# Sensor_Board_0d0ac80375c143579a8476edc31.net
KiCad netlist of a schematic drawn in EAGLE
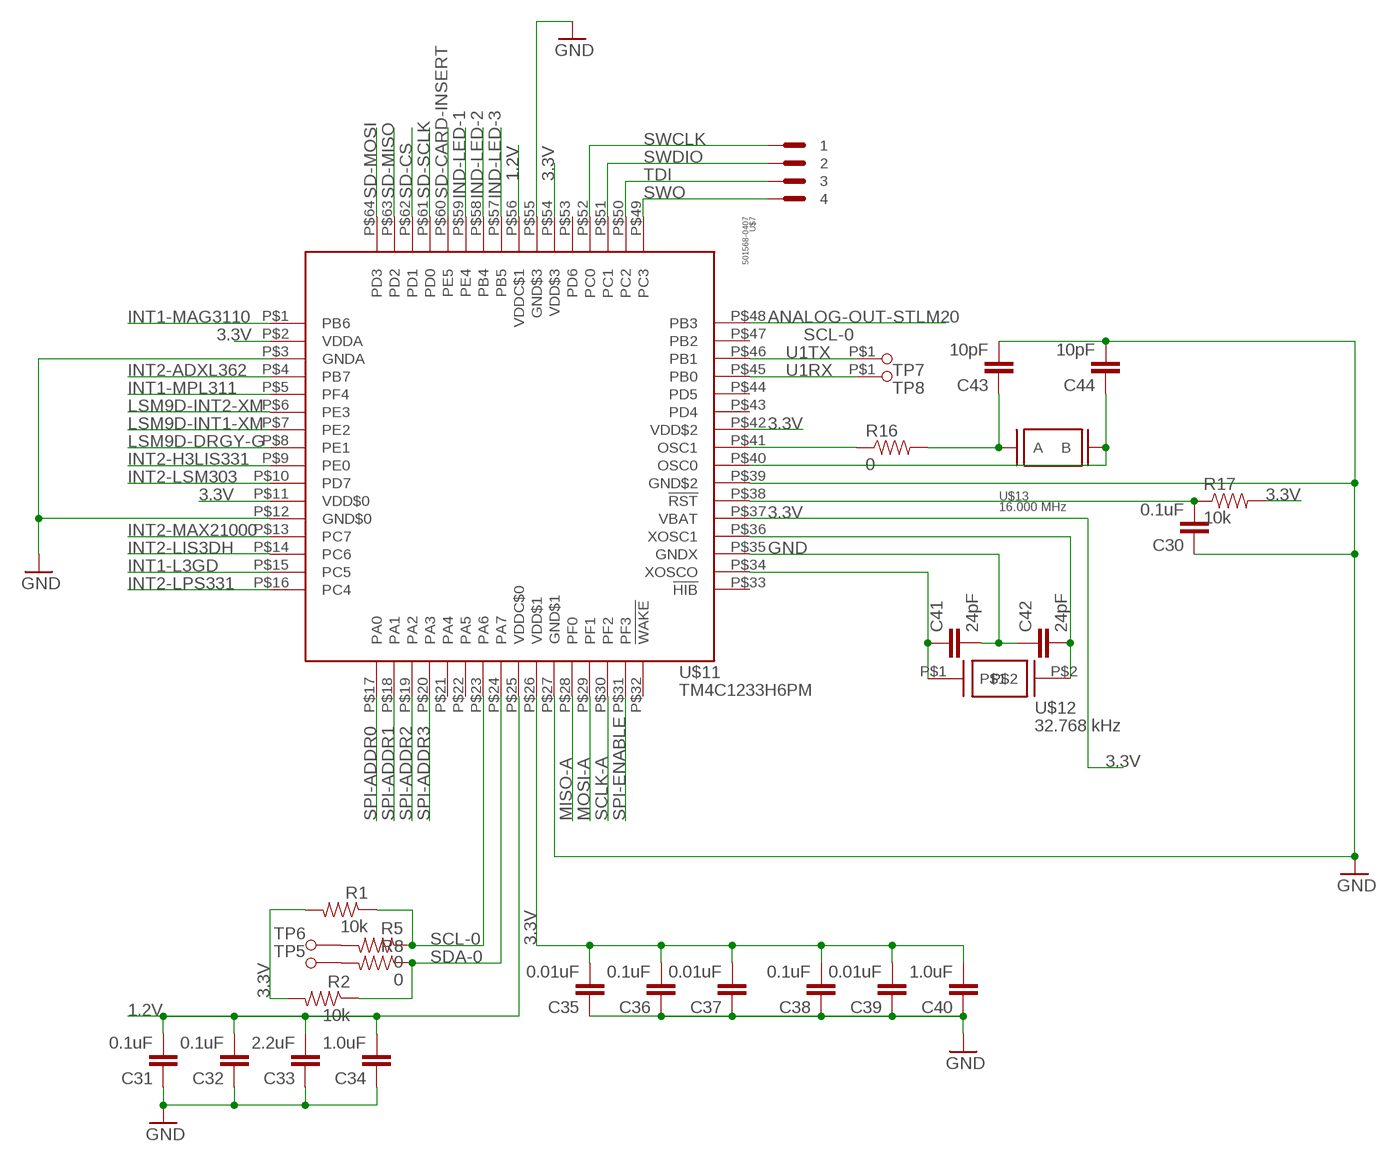
[diagram p0: schematic, sheet 1]
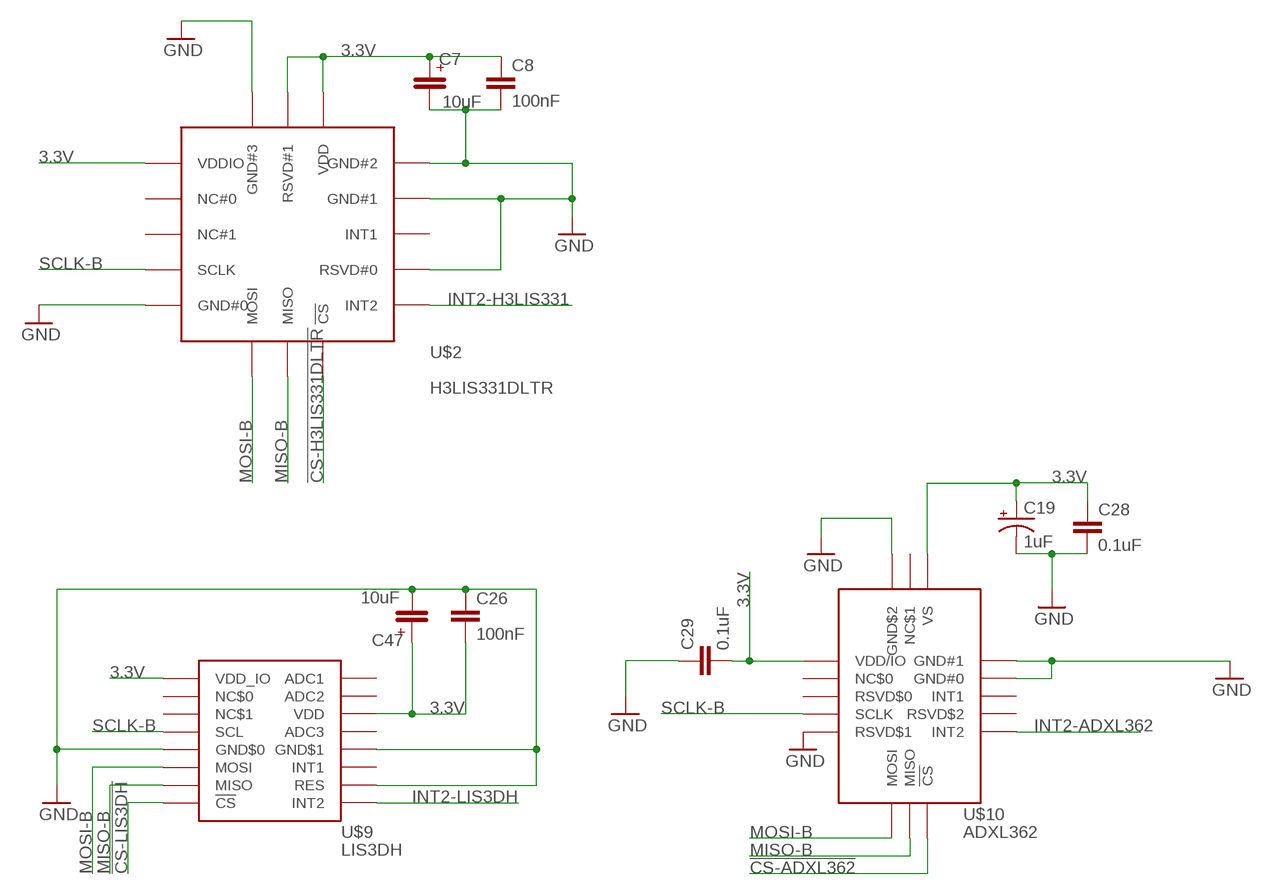
[diagram p1: schematic, sheet 2]
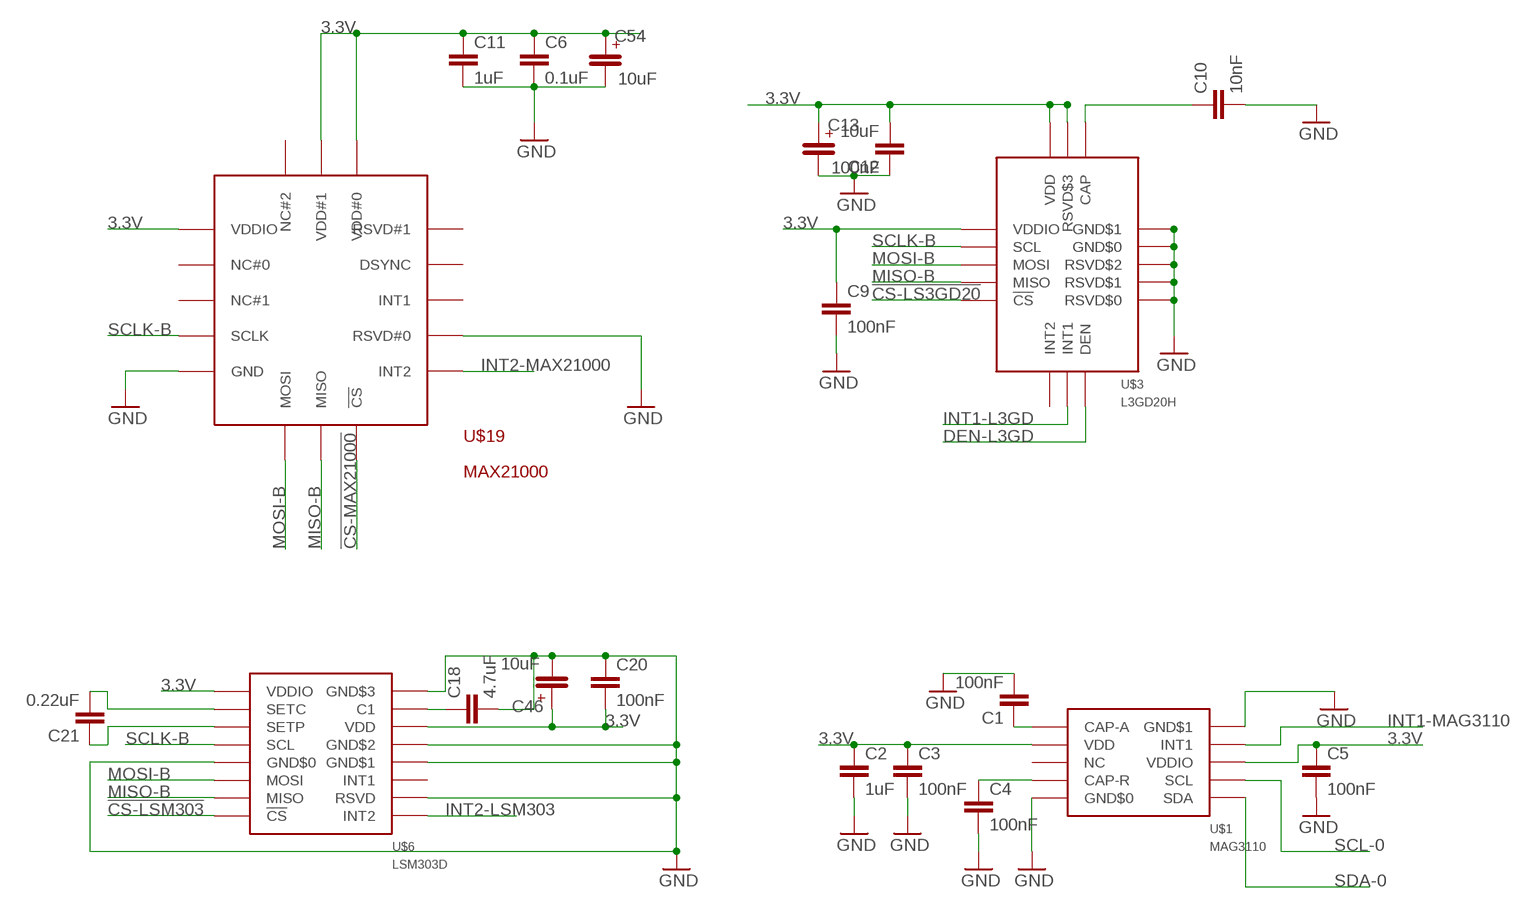
[diagram p2: schematic, sheet 3]
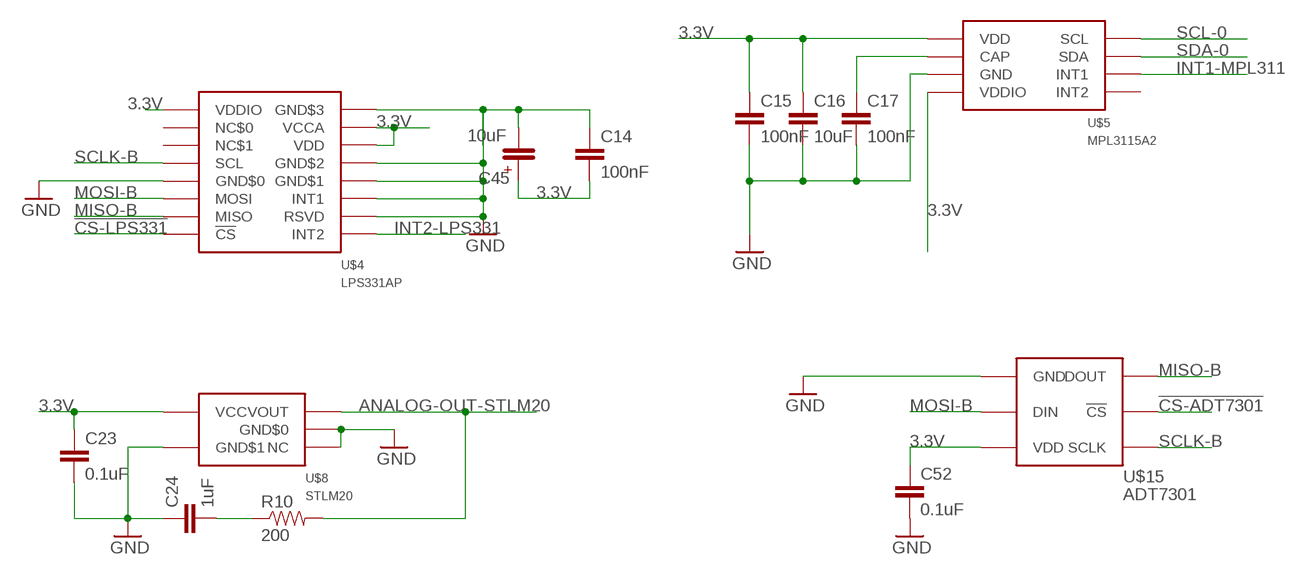
[diagram p3: schematic, sheet 4]
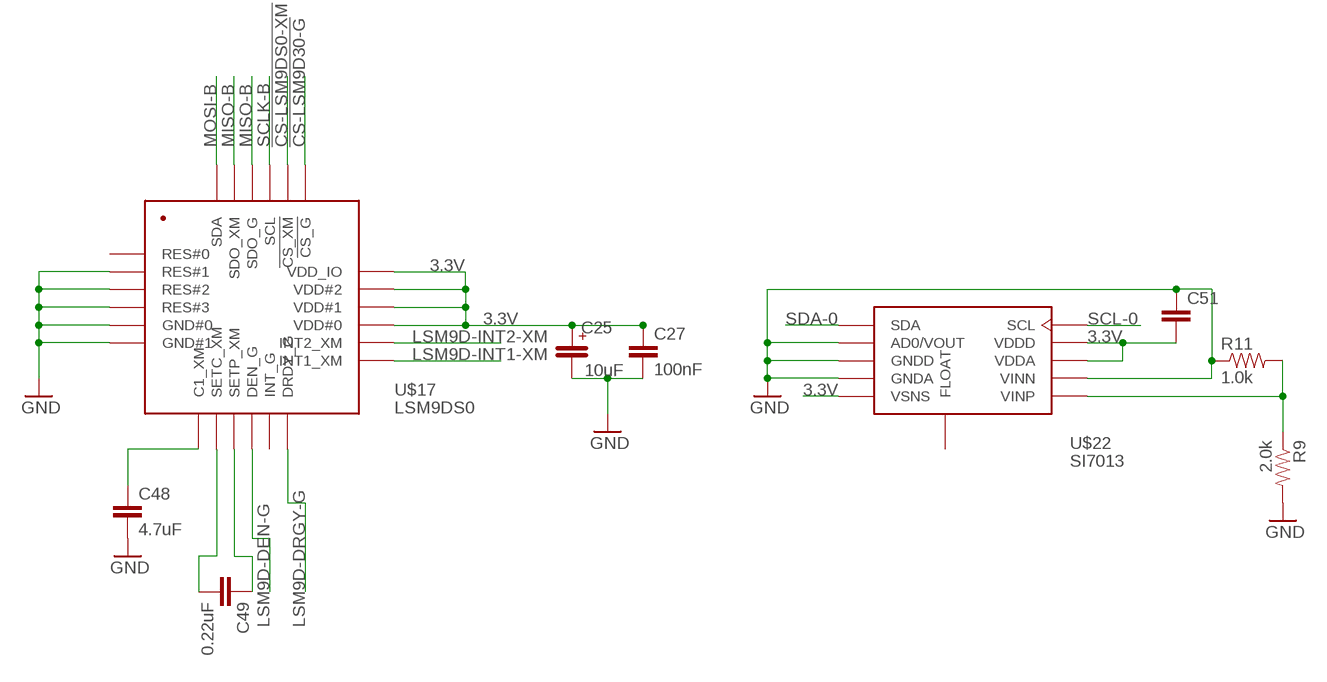
[diagram p4: schematic, sheet 5]
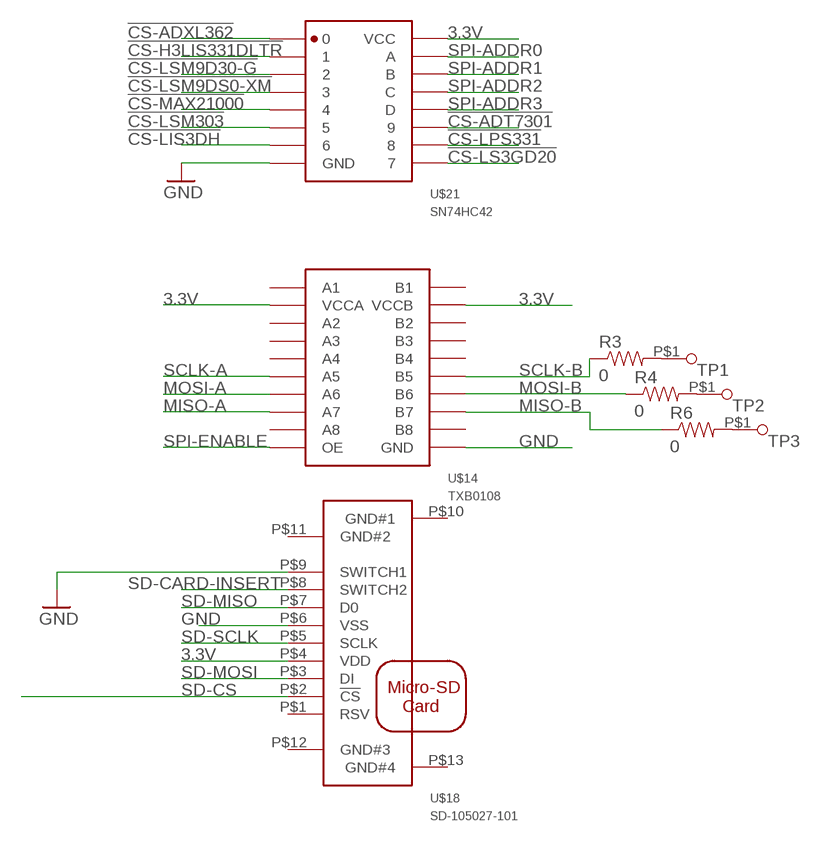
[diagram p5: schematic, sheet 6]
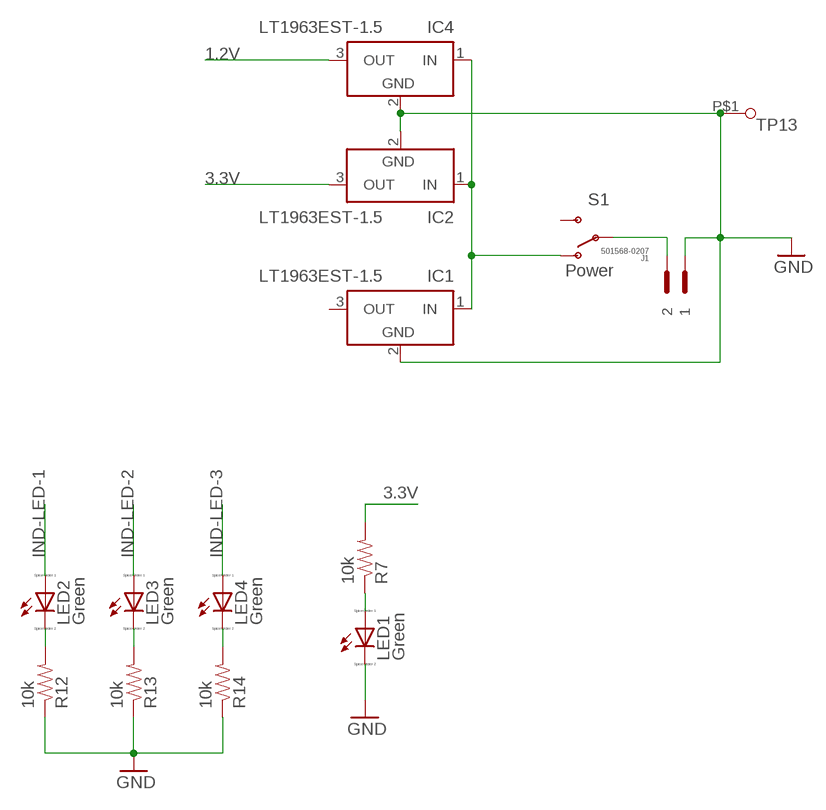
[diagram p6: schematic, sheet 7]

(export (version "E")
  (design (tool "Eeschema 10.0.6"))
  (components
    (comp (ref "C7")
      (value "10uF")
      (footprint "eagle-import:4.3X7.3SMD")
      (libsource (lib "eagle-import") (part "EEFCD0J100ER"))
    )
    (comp (ref "C8")
      (value "100nF")
      (footprint "eagle-import:C0402")
      (libsource (lib "eagle-import") (part "CAPACITOR0402"))
    )
    (comp (ref "C19")
      (value "1uF")
      (footprint "eagle-import:EIA6032")
      (libsource (lib "eagle-import") (part "CAP_POL6032"))
    )
    (comp (ref "C26")
      (value "100nF")
      (footprint "eagle-import:C0402")
      (libsource (lib "eagle-import") (part "CAPACITOR0402"))
    )
    (comp (ref "C28")
      (value "0.1uF")
      (footprint "eagle-import:C0402")
      (libsource (lib "eagle-import") (part "CAPACITOR0402"))
    )
    (comp (ref "C29")
      (value "0.1uF")
      (footprint "eagle-import:C0402")
      (libsource (lib "eagle-import") (part "CAPACITOR0402"))
    )
    (comp (ref "C47")
      (value "10uF")
      (footprint "eagle-import:4.3X7.3SMD")
      (libsource (lib "eagle-import") (part "EEFCD0J100ER"))
    )
    (comp (ref "U$2")
      (value "H3LIS331DLTR")
      (footprint "eagle-import:LGA-16(3X3)")
      (libsource (lib "eagle-import") (part "H3LIS331DLTR"))
    )
    (comp (ref "U$9")
      (value "LIS3DH")
      (footprint "eagle-import:LGA-16(3X3)")
      (libsource (lib "eagle-import") (part "LIS3DH"))
    )
    (comp (ref "U$10")
      (value "ADXL362")
      (footprint "eagle-import:LGA-16(3X3.25)")
      (libsource (lib "eagle-import") (part "ADXL362"))
    )
    (comp (ref "C25")
      (value "10uF")
      (footprint "eagle-import:4.3X7.3SMD")
      (libsource (lib "eagle-import") (part "EEFCD0J100ER"))
    )
    (comp (ref "C27")
      (value "100nF")
      (footprint "eagle-import:C0402")
      (libsource (lib "eagle-import") (part "CAPACITOR0402"))
    )
    (comp (ref "C48")
      (value "4.7uF")
      (footprint "eagle-import:C0402")
      (libsource (lib "eagle-import") (part "CAPACITOR0402"))
    )
    (comp (ref "C49")
      (value "0.22uF")
      (footprint "eagle-import:C0402")
      (libsource (lib "eagle-import") (part "CAPACITOR0402"))
    )
    (comp (ref "C51")
      (value "CAPACITOR0402")
      (footprint "eagle-import:C0402")
      (libsource (lib "eagle-import") (part "CAPACITOR0402"))
    )
    (comp (ref "R9")
      (value "2.0k")
      (footprint "eagle-import:R0402")
      (libsource (lib "eagle-import") (part "RESISTOR"))
    )
    (comp (ref "R11")
      (value "1.0k")
      (footprint "eagle-import:R0402")
      (libsource (lib "eagle-import") (part "RESISTOR"))
    )
    (comp (ref "U$17")
      (value "LSM9DS0")
      (footprint "eagle-import:LGA-24(4X4)")
      (libsource (lib "eagle-import") (part "LSM9DS0"))
    )
    (comp (ref "U$22")
      (value "SI7013")
      (footprint "eagle-import:DFN-10(3X3)")
      (libsource (lib "eagle-import") (part "SI7013"))
    )
    (comp (ref "C1")
      (value "100nF")
      (footprint "eagle-import:C0402")
      (libsource (lib "eagle-import") (part "CAPACITOR0402"))
    )
    (comp (ref "C2")
      (value "1uF")
      (footprint "eagle-import:C0402")
      (libsource (lib "eagle-import") (part "CAPACITOR0402"))
    )
    (comp (ref "C3")
      (value "100nF")
      (footprint "eagle-import:C0402")
      (libsource (lib "eagle-import") (part "CAPACITOR0402"))
    )
    (comp (ref "C4")
      (value "100nF")
      (footprint "eagle-import:C0402")
      (libsource (lib "eagle-import") (part "CAPACITOR0402"))
    )
    (comp (ref "C5")
      (value "100nF")
      (footprint "eagle-import:C0402")
      (libsource (lib "eagle-import") (part "CAPACITOR0402"))
    )
    (comp (ref "C6")
      (value "0.1uF")
      (footprint "eagle-import:C0402")
      (libsource (lib "eagle-import") (part "CAPACITOR0402"))
    )
    (comp (ref "C9")
      (value "100nF")
      (footprint "eagle-import:C0402")
      (libsource (lib "eagle-import") (part "CAPACITOR0402"))
    )
    (comp (ref "C10")
      (value "10nF")
      (footprint "eagle-import:C0402")
      (libsource (lib "eagle-import") (part "CAPACITOR0402"))
    )
    (comp (ref "C11")
      (value "1uF")
      (footprint "eagle-import:C0402")
      (libsource (lib "eagle-import") (part "CAPACITOR0402"))
    )
    (comp (ref "C12")
      (value "10uF")
      (footprint "eagle-import:C0402")
      (libsource (lib "eagle-import") (part "CAPACITOR0402"))
    )
    (comp (ref "C13")
      (value "100nF")
      (footprint "eagle-import:4.3X7.3SMD")
      (libsource (lib "eagle-import") (part "EEFCD0J100ER"))
    )
    (comp (ref "C18")
      (value "4.7uF")
      (footprint "eagle-import:C0402")
      (libsource (lib "eagle-import") (part "CAPACITOR0402"))
    )
    (comp (ref "C20")
      (value "100nF")
      (footprint "eagle-import:C0402")
      (libsource (lib "eagle-import") (part "CAPACITOR0402"))
    )
    (comp (ref "C21")
      (value "0.22uF")
      (footprint "eagle-import:C0402")
      (libsource (lib "eagle-import") (part "CAPACITOR0402"))
    )
    (comp (ref "C46")
      (value "10uF")
      (footprint "eagle-import:4.3X7.3SMD")
      (libsource (lib "eagle-import") (part "EEFCD0J100ER"))
    )
    (comp (ref "C54")
      (value "10uF")
      (footprint "eagle-import:4.3X7.3SMD")
      (libsource (lib "eagle-import") (part "EEFCD0J100ER"))
    )
    (comp (ref "U$1")
      (value "MAG3110")
      (footprint "eagle-import:DFN-10(2X2)")
      (libsource (lib "eagle-import") (part "MAG3110"))
    )
    (comp (ref "U$3")
      (value "L3GD20H")
      (footprint "eagle-import:LGA-16(3X3)")
      (libsource (lib "eagle-import") (part "L3GD20H"))
    )
    (comp (ref "U$6")
      (value "LSM303D")
      (footprint "eagle-import:LGA-16(3X3)")
      (libsource (lib "eagle-import") (part "LSM303D"))
    )
    (comp (ref "U$19")
      (value "MAX21000")
      (footprint "eagle-import:LGA-16(3X3)")
      (libsource (lib "eagle-import") (part "MAX21000"))
    )
    (comp (ref "C14")
      (value "100nF")
      (footprint "eagle-import:C0402")
      (libsource (lib "eagle-import") (part "CAPACITOR0402"))
    )
    (comp (ref "C15")
      (value "100nF")
      (footprint "eagle-import:C0402")
      (libsource (lib "eagle-import") (part "CAPACITOR0402"))
    )
    (comp (ref "C16")
      (value "10uF")
      (footprint "eagle-import:C0402")
      (libsource (lib "eagle-import") (part "CAPACITOR0402"))
    )
    (comp (ref "C17")
      (value "100nF")
      (footprint "eagle-import:C0402")
      (libsource (lib "eagle-import") (part "CAPACITOR0402"))
    )
    (comp (ref "C23")
      (value "0.1uF")
      (footprint "eagle-import:C0402")
      (libsource (lib "eagle-import") (part "CAPACITOR0402"))
    )
    (comp (ref "C24")
      (value "1uF")
      (footprint "eagle-import:C0402")
      (libsource (lib "eagle-import") (part "CAPACITOR0402"))
    )
    (comp (ref "C45")
      (value "10uF")
      (footprint "eagle-import:4.3X7.3SMD")
      (libsource (lib "eagle-import") (part "EEFCD0J100ER"))
    )
    (comp (ref "C52")
      (value "0.1uF")
      (footprint "eagle-import:C0402")
      (libsource (lib "eagle-import") (part "CAPACITOR0402"))
    )
    (comp (ref "R10")
      (value "200")
      (footprint "eagle-import:R0402")
      (libsource (lib "eagle-import") (part "RESISTOR"))
    )
    (comp (ref "U$4")
      (value "LPS331AP")
      (footprint "eagle-import:LGA-16(3X3)")
      (libsource (lib "eagle-import") (part "LPS331AP"))
    )
    (comp (ref "U$5")
      (value "MPL3115A2")
      (footprint "eagle-import:LGA-8(5X3)")
      (libsource (lib "eagle-import") (part "MPL3115A2"))
    )
    (comp (ref "U$8")
      (value "STLM20")
      (footprint "eagle-import:SOT323-5L")
      (libsource (lib "eagle-import") (part "STLM20"))
    )
    (comp (ref "U$15")
      (value "ADT7301")
      (footprint "eagle-import:SOT23-6")
      (libsource (lib "eagle-import") (part "ADT7301"))
    )
    (comp (ref "C30")
      (value "0.1uF")
      (footprint "eagle-import:C0402")
      (libsource (lib "eagle-import") (part "CAPACITOR0402"))
    )
    (comp (ref "C31")
      (value "0.1uF")
      (footprint "eagle-import:C0402")
      (libsource (lib "eagle-import") (part "CAPACITOR0402"))
    )
    (comp (ref "C32")
      (value "0.1uF")
      (footprint "eagle-import:C0402")
      (libsource (lib "eagle-import") (part "CAPACITOR0402"))
    )
    (comp (ref "C33")
      (value "2.2uF")
      (footprint "eagle-import:C0402")
      (libsource (lib "eagle-import") (part "CAPACITOR0402"))
    )
    (comp (ref "C34")
      (value "1.0uF")
      (footprint "eagle-import:C0402")
      (libsource (lib "eagle-import") (part "CAPACITOR0402"))
    )
    (comp (ref "C35")
      (value "0.01uF")
      (footprint "eagle-import:C0402")
      (libsource (lib "eagle-import") (part "CAPACITOR0402"))
    )
    (comp (ref "C36")
      (value "0.1uF")
      (footprint "eagle-import:C0402")
      (libsource (lib "eagle-import") (part "CAPACITOR0402"))
    )
    (comp (ref "C37")
      (value "0.01uF")
      (footprint "eagle-import:C0402")
      (libsource (lib "eagle-import") (part "CAPACITOR0402"))
    )
    (comp (ref "C38")
      (value "0.1uF")
      (footprint "eagle-import:C0402")
      (libsource (lib "eagle-import") (part "CAPACITOR0402"))
    )
    (comp (ref "C39")
      (value "0.01uF")
      (footprint "eagle-import:C0402")
      (libsource (lib "eagle-import") (part "CAPACITOR0402"))
    )
    (comp (ref "C40")
      (value "1.0uF")
      (footprint "eagle-import:C0402")
      (libsource (lib "eagle-import") (part "CAPACITOR0402"))
    )
    (comp (ref "C41")
      (value "24pF")
      (footprint "eagle-import:C0402")
      (libsource (lib "eagle-import") (part "CAPACITOR0402"))
    )
    (comp (ref "C42")
      (value "24pF")
      (footprint "eagle-import:C0402")
      (libsource (lib "eagle-import") (part "CAPACITOR0402"))
    )
    (comp (ref "C43")
      (value "10pF")
      (footprint "eagle-import:C0402")
      (libsource (lib "eagle-import") (part "CAPACITOR0402"))
    )
    (comp (ref "C44")
      (value "10pF")
      (footprint "eagle-import:C0402")
      (libsource (lib "eagle-import") (part "CAPACITOR0402"))
    )
    (comp (ref "R1")
      (value "10k")
      (footprint "eagle-import:R0402")
      (libsource (lib "eagle-import") (part "RESISTOR"))
    )
    (comp (ref "R2")
      (value "10k")
      (footprint "eagle-import:R0402")
      (libsource (lib "eagle-import") (part "RESISTOR"))
    )
    (comp (ref "R5")
      (value "0")
      (footprint "eagle-import:R0402")
      (libsource (lib "eagle-import") (part "RESISTOR"))
    )
    (comp (ref "R8")
      (value "0")
      (footprint "eagle-import:R0402")
      (libsource (lib "eagle-import") (part "RESISTOR"))
    )
    (comp (ref "R16")
      (value "0")
      (footprint "eagle-import:R0402")
      (libsource (lib "eagle-import") (part "RESISTOR"))
    )
    (comp (ref "R17")
      (value "10k")
      (footprint "eagle-import:R0402")
      (libsource (lib "eagle-import") (part "RESISTOR"))
    )
    (comp (ref "TP5")
      (value "TESTPAD(ROUND)")
      (footprint "eagle-import:TESTPAD(ROUND)")
      (libsource (lib "eagle-import") (part "TESTPAD(ROUND)"))
    )
    (comp (ref "TP6")
      (value "TESTPAD(ROUND)")
      (footprint "eagle-import:TESTPAD(ROUND)")
      (libsource (lib "eagle-import") (part "TESTPAD(ROUND)"))
    )
    (comp (ref "TP7")
      (value "TESTPAD(ROUND)")
      (footprint "eagle-import:TESTPAD(ROUND)")
      (libsource (lib "eagle-import") (part "Kas-Passives_TESTPAD(ROUND)"))
    )
    (comp (ref "TP8")
      (value "TESTPAD(ROUND)")
      (footprint "eagle-import:TESTPAD(ROUND)")
      (libsource (lib "eagle-import") (part "Kas-Passives_TESTPAD(ROUND)"))
    )
    (comp (ref "U$7")
      (value "501568-0407")
      (footprint "eagle-import:501568-0407")
      (libsource (lib "eagle-import") (part "501568-0407"))
    )
    (comp (ref "U$11")
      (value "TM4C1233H6PM")
      (footprint "eagle-import:S-PQFP-G64")
      (libsource (lib "eagle-import") (part "TM4C1233H6PM"))
    )
    (comp (ref "U$12")
      (value "32.768 kHz")
      (footprint "eagle-import:2-SMD(3.2X1.5)")
      (libsource (lib "eagle-import") (part "ABS07L"))
    )
    (comp (ref "U$13")
      (value "16.000 MHz")
      (footprint "eagle-import:4-SMD(3.2X2.5)")
      (libsource (lib "eagle-import") (part "NX3225GA"))
    )
    (comp (ref "R3")
      (value "0")
      (footprint "eagle-import:R0402")
      (libsource (lib "eagle-import") (part "RESISTOR"))
    )
    (comp (ref "R4")
      (value "0")
      (footprint "eagle-import:R0402")
      (libsource (lib "eagle-import") (part "RESISTOR"))
    )
    (comp (ref "R6")
      (value "0")
      (footprint "eagle-import:R0402")
      (libsource (lib "eagle-import") (part "RESISTOR"))
    )
    (comp (ref "TP1")
      (value "TESTPAD(ROUND)")
      (footprint "eagle-import:TESTPAD(ROUND)")
      (libsource (lib "eagle-import") (part "Kas-Passives_TESTPAD(ROUND)"))
    )
    (comp (ref "TP2")
      (value "TESTPAD(ROUND)")
      (footprint "eagle-import:TESTPAD(ROUND)")
      (libsource (lib "eagle-import") (part "Kas-Passives_TESTPAD(ROUND)"))
    )
    (comp (ref "TP3")
      (value "TESTPAD(ROUND)")
      (footprint "eagle-import:TESTPAD(ROUND)")
      (libsource (lib "eagle-import") (part "Kas-Passives_TESTPAD(ROUND)"))
    )
    (comp (ref "U$14")
      (value "TXB0108")
      (footprint "eagle-import:TSSOP-(PW)-20")
      (libsource (lib "eagle-import") (part "TXB0108"))
    )
    (comp (ref "U$18")
      (value "SD-105027-101")
      (footprint "eagle-import:SD-105027-1001")
      (libsource (lib "eagle-import") (part "SD-105027-101"))
    )
    (comp (ref "U$21")
      (value "SN74HC42")
      (footprint "eagle-import:SOIC-16")
      (libsource (lib "eagle-import") (part "SN74HC42"))
    )
    (comp (ref "IC1")
      (value "LT1963EST-1.5")
      (footprint "eagle-import:SOT223")
      (libsource (lib "eagle-import") (part "LT1963EST-1.5"))
    )
    (comp (ref "IC2")
      (value "LT1963EST-1.5")
      (footprint "eagle-import:SOT223")
      (libsource (lib "eagle-import") (part "LT1963EST-1.5"))
    )
    (comp (ref "IC4")
      (value "LT1963EST-1.5")
      (footprint "eagle-import:SOT223")
      (libsource (lib "eagle-import") (part "LT1963EST-1.5"))
    )
    (comp (ref "J1")
      (value "501568-0207")
      (footprint "eagle-import:501568-0207")
      (libsource (lib "eagle-import") (part "501568-0207"))
    )
    (comp (ref "LED1")
      (value "Green")
      (footprint "eagle-import:LED_SML0603")
      (libsource (lib "eagle-import") (part "LED_ESML0603"))
    )
    (comp (ref "LED2")
      (value "Green")
      (footprint "eagle-import:LED_SML0603")
      (libsource (lib "eagle-import") (part "LED_ESML0603"))
    )
    (comp (ref "LED3")
      (value "Green")
      (footprint "eagle-import:LED_SML0603")
      (libsource (lib "eagle-import") (part "LED_ESML0603"))
    )
    (comp (ref "LED4")
      (value "Green")
      (footprint "eagle-import:LED_SML0603")
      (libsource (lib "eagle-import") (part "LED_ESML0603"))
    )
    (comp (ref "R7")
      (value "10k")
      (footprint "eagle-import:R0402")
      (libsource (lib "eagle-import") (part "RESISTOR"))
    )
    (comp (ref "R12")
      (value "10k")
      (footprint "eagle-import:R0402")
      (libsource (lib "eagle-import") (part "RESISTOR"))
    )
    (comp (ref "R13")
      (value "10k")
      (footprint "eagle-import:R0402")
      (libsource (lib "eagle-import") (part "RESISTOR"))
    )
    (comp (ref "R14")
      (value "10k")
      (footprint "eagle-import:R0402")
      (libsource (lib "eagle-import") (part "RESISTOR"))
    )
    (comp (ref "S1")
      (value "Power")
      (footprint "eagle-import:SWITCH-SPST-SMD-A")
      (libsource (lib "eagle-import") (part "SWITCH-SPDT-SMD-A"))
    )
    (comp (ref "TP13")
      (value "TESTPAD(ROUND)")
      (footprint "eagle-import:TESTPAD(ROUND)")
      (libsource (lib "eagle-import") (part "Kas-Passives_TESTPAD(ROUND)"))
    )
  )
  (nets
    (net (code "1") (name "1.2V") (class "Default")
      (node (ref "C31") (pin "2") (pinfunction "2_2") (pintype "passive"))
      (node (ref "C32") (pin "2") (pinfunction "2_2") (pintype "passive"))
      (node (ref "C33") (pin "2") (pinfunction "2_2") (pintype "passive"))
      (node (ref "C34") (pin "2") (pinfunction "2_2") (pintype "passive"))
      (node (ref "IC4") (pin "3") (pinfunction "OUT_3") (pintype "output"))
      (node (ref "U$11") (pin "P$25") (pinfunction "VDDC$0_P$25") (pintype "bidirectional"))
      (node (ref "U$11") (pin "P$56") (pinfunction "VDDC$1_P$56") (pintype "bidirectional"))
    )
    (net (code "2") (name "3.3V") (class "Default")
      (node (ref "C11") (pin "1") (pinfunction "1_1") (pintype "passive"))
      (node (ref "C12") (pin "2") (pinfunction "2_2") (pintype "passive"))
      (node (ref "C13") (pin "P$1") (pintype "bidirectional"))
      (node (ref "C14") (pin "2") (pinfunction "2_2") (pintype "passive"))
      (node (ref "C15") (pin "1") (pinfunction "1_1") (pintype "passive"))
      (node (ref "C16") (pin "1") (pinfunction "1_1") (pintype "passive"))
      (node (ref "C19") (pin "P$1") (pinfunction "+_P$1") (pintype "passive"))
      (node (ref "C2") (pin "1") (pinfunction "1_1") (pintype "passive"))
      (node (ref "C20") (pin "2") (pinfunction "2_2") (pintype "passive"))
      (node (ref "C23") (pin "1") (pinfunction "1_1") (pintype "passive"))
      (node (ref "C25") (pin "P$1") (pintype "bidirectional"))
      (node (ref "C26") (pin "2") (pinfunction "2_2") (pintype "passive"))
      (node (ref "C27") (pin "1") (pinfunction "1_1") (pintype "passive"))
      (node (ref "C28") (pin "1") (pinfunction "1_1") (pintype "passive"))
      (node (ref "C29") (pin "2") (pinfunction "2_2") (pintype "passive"))
      (node (ref "C3") (pin "1") (pinfunction "1_1") (pintype "passive"))
      (node (ref "C35") (pin "2") (pinfunction "2_2") (pintype "passive"))
      (node (ref "C36") (pin "2") (pinfunction "2_2") (pintype "passive"))
      (node (ref "C37") (pin "2") (pinfunction "2_2") (pintype "passive"))
      (node (ref "C38") (pin "2") (pinfunction "2_2") (pintype "passive"))
      (node (ref "C39") (pin "2") (pinfunction "2_2") (pintype "passive"))
      (node (ref "C40") (pin "2") (pinfunction "2_2") (pintype "passive"))
      (node (ref "C45") (pin "P$1") (pintype "bidirectional"))
      (node (ref "C46") (pin "P$1") (pintype "bidirectional"))
      (node (ref "C47") (pin "P$1") (pintype "bidirectional"))
      (node (ref "C5") (pin "1") (pinfunction "1_1") (pintype "passive"))
      (node (ref "C51") (pin "2") (pinfunction "2_2") (pintype "passive"))
      (node (ref "C52") (pin "1") (pinfunction "1_1") (pintype "passive"))
      (node (ref "C54") (pin "P$1") (pintype "bidirectional"))
      (node (ref "C6") (pin "1") (pinfunction "1_1") (pintype "passive"))
      (node (ref "C7") (pin "P$1") (pintype "bidirectional"))
      (node (ref "C8") (pin "1") (pinfunction "1_1") (pintype "passive"))
      (node (ref "C9") (pin "1") (pinfunction "1_1") (pintype "passive"))
      (node (ref "IC2") (pin "3") (pinfunction "OUT_3") (pintype "output"))
      (node (ref "R1") (pin "2") (pinfunction "2_2") (pintype "passive"))
      (node (ref "R17") (pin "2") (pinfunction "2_2") (pintype "passive"))
      (node (ref "R2") (pin "2") (pinfunction "2_2") (pintype "passive"))
      (node (ref "R7") (pin "2") (pinfunction "2_2") (pintype "passive"))
      (node (ref "U$1") (pin "P$2") (pinfunction "VDD_P$2") (pintype "bidirectional"))
      (node (ref "U$1") (pin "P$8") (pinfunction "VDDIO_P$8") (pintype "bidirectional"))
      (node (ref "U$10") (pin "P$1") (pinfunction "VDD/IO_P$1") (pintype "bidirectional"))
      (node (ref "U$10") (pin "P$14") (pinfunction "VS_P$14") (pintype "bidirectional"))
      (node (ref "U$11") (pin "P$11") (pinfunction "VDD$0_P$11") (pintype "bidirectional"))
      (node (ref "U$11") (pin "P$2") (pinfunction "VDDA_P$2") (pintype "bidirectional"))
      (node (ref "U$11") (pin "P$26") (pinfunction "VDD$1_P$26") (pintype "bidirectional"))
      (node (ref "U$11") (pin "P$37") (pinfunction "VBAT_P$37") (pintype "bidirectional"))
      (node (ref "U$11") (pin "P$42") (pinfunction "VDD$2_P$42") (pintype "bidirectional"))
      (node (ref "U$11") (pin "P$54") (pinfunction "VDD$3_P$54") (pintype "bidirectional"))
      (node (ref "U$14") (pin "P$19") (pinfunction "VCCB_P$19") (pintype "bidirectional"))
      (node (ref "U$14") (pin "P$2") (pinfunction "VCCA_P$2") (pintype "bidirectional"))
      (node (ref "U$15") (pin "P$3") (pinfunction "VDD_P$3") (pintype "bidirectional"))
      (node (ref "U$17") (pin "P$15") (pinfunction "VDD#0_P$15") (pintype "bidirectional"))
      (node (ref "U$17") (pin "P$16") (pinfunction "VDD#1_P$16") (pintype "bidirectional"))
      (node (ref "U$17") (pin "P$17") (pinfunction "VDD#2_P$17") (pintype "bidirectional"))
      (node (ref "U$17") (pin "P$18") (pinfunction "VDD_IO_P$18") (pintype "bidirectional"))
      (node (ref "U$18") (pin "P$4") (pinfunction "VDD_P$4") (pintype "bidirectional"))
      (node (ref "U$19") (pin "P$1") (pinfunction "VDDIO_P$1") (pintype "bidirectional"))
      (node (ref "U$19") (pin "P$14") (pinfunction "VDD#0_P$14") (pintype "bidirectional"))
      (node (ref "U$19") (pin "P$15") (pinfunction "VDD#1_P$15") (pintype "bidirectional"))
      (node (ref "U$2") (pin "P$1") (pinfunction "VDDIO_P$1") (pintype "bidirectional"))
      (node (ref "U$2") (pin "P$14") (pinfunction "VDD_P$14") (pintype "bidirectional"))
      (node (ref "U$2") (pin "P$15") (pinfunction "RSVD#1_P$15") (pintype "bidirectional"))
      (node (ref "U$21") (pin "P$16") (pinfunction "VCC_P$16") (pintype "bidirectional"))
      (node (ref "U$22") (pin "P$5") (pinfunction "VSNS_P$5") (pintype "bidirectional"))
      (node (ref "U$22") (pin "P$8") (pinfunction "VDDA_P$8") (pintype "bidirectional"))
      (node (ref "U$22") (pin "P$9") (pinfunction "VDDD_P$9") (pintype "bidirectional"))
      (node (ref "U$3") (pin "P$1") (pinfunction "VDDIO_P$1") (pintype "bidirectional"))
      (node (ref "U$3") (pin "P$15") (pinfunction "RSVD$3_P$15") (pintype "bidirectional"))
      (node (ref "U$3") (pin "P$16") (pinfunction "VDD_P$16") (pintype "bidirectional"))
      (node (ref "U$4") (pin "P$1") (pinfunction "VDDIO_P$1") (pintype "bidirectional"))
      (node (ref "U$4") (pin "P$14") (pinfunction "VDD_P$14") (pintype "bidirectional"))
      (node (ref "U$4") (pin "P$15") (pinfunction "VCCA_P$15") (pintype "bidirectional"))
      (node (ref "U$5") (pin "P$1") (pinfunction "VDD_P$1") (pintype "bidirectional"))
      (node (ref "U$5") (pin "P$4") (pinfunction "VDDIO_P$4") (pintype "bidirectional"))
      (node (ref "U$6") (pin "P$1") (pinfunction "VDDIO_P$1") (pintype "bidirectional"))
      (node (ref "U$6") (pin "P$14") (pinfunction "VDD_P$14") (pintype "bidirectional"))
      (node (ref "U$8") (pin "P$4") (pinfunction "VCC_P$4") (pintype "bidirectional"))
      (node (ref "U$9") (pin "P$1") (pinfunction "VDD_IO_P$1") (pintype "bidirectional"))
      (node (ref "U$9") (pin "P$14") (pinfunction "VDD_P$14") (pintype "bidirectional"))
    )
    (net (code "3") (name "ANALOG-OUT-STLM20") (class "Default")
      (node (ref "R10") (pin "2") (pinfunction "2_2") (pintype "passive"))
      (node (ref "U$11") (pin "P$48") (pinfunction "PB3_P$48") (pintype "bidirectional"))
      (node (ref "U$8") (pin "P$3") (pinfunction "VOUT_P$3") (pintype "bidirectional"))
    )
    (net (code "4") (name "DEN-L3GD") (class "Default")
      (node (ref "U$3") (pin "P$8") (pinfunction "DEN_P$8") (pintype "bidirectional"))
    )
    (net (code "5") (name "GND") (class "Default")
      (node (ref "C1") (pin "2") (pinfunction "2_2") (pintype "passive"))
      (node (ref "C10") (pin "2") (pinfunction "2_2") (pintype "passive"))
      (node (ref "C11") (pin "2") (pinfunction "2_2") (pintype "passive"))
      (node (ref "C12") (pin "1") (pinfunction "1_1") (pintype "passive"))
      (node (ref "C13") (pin "P$2") (pintype "bidirectional"))
      (node (ref "C14") (pin "1") (pinfunction "1_1") (pintype "passive"))
      (node (ref "C15") (pin "2") (pinfunction "2_2") (pintype "passive"))
      (node (ref "C16") (pin "2") (pinfunction "2_2") (pintype "passive"))
      (node (ref "C17") (pin "2") (pinfunction "2_2") (pintype "passive"))
      (node (ref "C18") (pin "2") (pinfunction "2_2") (pintype "passive"))
      (node (ref "C19") (pin "P$2") (pinfunction "-_P$2") (pintype "passive"))
      (node (ref "C2") (pin "2") (pinfunction "2_2") (pintype "passive"))
      (node (ref "C20") (pin "1") (pinfunction "1_1") (pintype "passive"))
      (node (ref "C23") (pin "2") (pinfunction "2_2") (pintype "passive"))
      (node (ref "C24") (pin "1") (pinfunction "1_1") (pintype "passive"))
      (node (ref "C25") (pin "P$2") (pintype "bidirectional"))
      (node (ref "C26") (pin "1") (pinfunction "1_1") (pintype "passive"))
      (node (ref "C27") (pin "2") (pinfunction "2_2") (pintype "passive"))
      (node (ref "C28") (pin "2") (pinfunction "2_2") (pintype "passive"))
      (node (ref "C29") (pin "1") (pinfunction "1_1") (pintype "passive"))
      (node (ref "C3") (pin "2") (pinfunction "2_2") (pintype "passive"))
      (node (ref "C30") (pin "1") (pinfunction "1_1") (pintype "passive"))
      (node (ref "C31") (pin "1") (pinfunction "1_1") (pintype "passive"))
      (node (ref "C32") (pin "1") (pinfunction "1_1") (pintype "passive"))
      (node (ref "C33") (pin "1") (pinfunction "1_1") (pintype "passive"))
      (node (ref "C34") (pin "1") (pinfunction "1_1") (pintype "passive"))
      (node (ref "C35") (pin "1") (pinfunction "1_1") (pintype "passive"))
      (node (ref "C36") (pin "1") (pinfunction "1_1") (pintype "passive"))
      (node (ref "C37") (pin "1") (pinfunction "1_1") (pintype "passive"))
      (node (ref "C38") (pin "1") (pinfunction "1_1") (pintype "passive"))
      (node (ref "C39") (pin "1") (pinfunction "1_1") (pintype "passive"))
      (node (ref "C4") (pin "2") (pinfunction "2_2") (pintype "passive"))
      (node (ref "C40") (pin "1") (pinfunction "1_1") (pintype "passive"))
      (node (ref "C41") (pin "2") (pinfunction "2_2") (pintype "passive"))
      (node (ref "C42") (pin "1") (pinfunction "1_1") (pintype "passive"))
      (node (ref "C43") (pin "2") (pinfunction "2_2") (pintype "passive"))
      (node (ref "C44") (pin "2") (pinfunction "2_2") (pintype "passive"))
      (node (ref "C45") (pin "P$2") (pintype "bidirectional"))
      (node (ref "C46") (pin "P$2") (pintype "bidirectional"))
      (node (ref "C47") (pin "P$2") (pintype "bidirectional"))
      (node (ref "C48") (pin "2") (pinfunction "2_2") (pintype "passive"))
      (node (ref "C5") (pin "2") (pinfunction "2_2") (pintype "passive"))
      (node (ref "C51") (pin "1") (pinfunction "1_1") (pintype "passive"))
      (node (ref "C52") (pin "2") (pinfunction "2_2") (pintype "passive"))
      (node (ref "C54") (pin "P$2") (pintype "bidirectional"))
      (node (ref "C6") (pin "2") (pinfunction "2_2") (pintype "passive"))
      (node (ref "C7") (pin "P$2") (pintype "bidirectional"))
      (node (ref "C8") (pin "2") (pinfunction "2_2") (pintype "passive"))
      (node (ref "C9") (pin "2") (pinfunction "2_2") (pintype "passive"))
      (node (ref "IC1") (pin "2") (pinfunction "GND_2") (pintype "power_in"))
      (node (ref "IC2") (pin "2") (pinfunction "GND_2") (pintype "power_in"))
      (node (ref "IC4") (pin "2") (pinfunction "GND_2") (pintype "power_in"))
      (node (ref "J1") (pin "P$1") (pinfunction "1_P$1") (pintype "bidirectional"))
      (node (ref "LED1") (pin "C") (pinfunction "C_C") (pintype "passive"))
      (node (ref "R11") (pin "1") (pinfunction "1_1") (pintype "passive"))
      (node (ref "R12") (pin "1") (pinfunction "1_1") (pintype "passive"))
      (node (ref "R13") (pin "1") (pinfunction "1_1") (pintype "passive"))
      (node (ref "R14") (pin "1") (pinfunction "1_1") (pintype "passive"))
      (node (ref "R9") (pin "2") (pinfunction "2_2") (pintype "passive"))
      (node (ref "TP13") (pin "P$1") (pinfunction "P$1_P$1") (pintype "bidirectional"))
      (node (ref "U$1") (pin "P$10") (pinfunction "GND$1_P$10") (pintype "bidirectional"))
      (node (ref "U$1") (pin "P$5") (pinfunction "GND$0_P$5") (pintype "bidirectional"))
      (node (ref "U$10") (pin "P$12") (pinfunction "GND#0_P$12") (pintype "bidirectional"))
      (node (ref "U$10") (pin "P$13") (pinfunction "GND#1_P$13") (pintype "bidirectional"))
      (node (ref "U$10") (pin "P$16") (pinfunction "GND$2_P$16") (pintype "bidirectional"))
      (node (ref "U$10") (pin "P$5") (pinfunction "RSVD$1_P$5") (pintype "bidirectional"))
      (node (ref "U$11") (pin "P$12") (pinfunction "GND$0_P$12") (pintype "bidirectional"))
      (node (ref "U$11") (pin "P$27") (pinfunction "GND$1_P$27") (pintype "bidirectional"))
      (node (ref "U$11") (pin "P$3") (pinfunction "GNDA_P$3") (pintype "bidirectional"))
      (node (ref "U$11") (pin "P$35") (pinfunction "GNDX_P$35") (pintype "bidirectional"))
      (node (ref "U$11") (pin "P$39") (pinfunction "GND$2_P$39") (pintype "bidirectional"))
      (node (ref "U$11") (pin "P$55") (pinfunction "GND$3_P$55") (pintype "bidirectional"))
      (node (ref "U$14") (pin "P$11") (pinfunction "GND_P$11") (pintype "bidirectional"))
      (node (ref "U$15") (pin "P$1") (pinfunction "GND_P$1") (pintype "bidirectional"))
      (node (ref "U$17") (pin "P$2") (pinfunction "RES#1_P$2") (pintype "bidirectional"))
      (node (ref "U$17") (pin "P$3") (pinfunction "RES#2_P$3") (pintype "bidirectional"))
      (node (ref "U$17") (pin "P$4") (pinfunction "RES#3_P$4") (pintype "bidirectional"))
      (node (ref "U$17") (pin "P$5") (pinfunction "GND#0_P$5") (pintype "bidirectional"))
      (node (ref "U$17") (pin "P$6") (pinfunction "GND#1_P$6") (pintype "bidirectional"))
      (node (ref "U$18") (pin "P$6") (pinfunction "VSS_P$6") (pintype "bidirectional"))
      (node (ref "U$18") (pin "P$9") (pinfunction "SWITCH1_P$9") (pintype "bidirectional"))
      (node (ref "U$19") (pin "P$10") (pinfunction "RSVD#0_P$10") (pintype "bidirectional"))
      (node (ref "U$19") (pin "P$5") (pinfunction "GND_P$5") (pintype "bidirectional"))
      (node (ref "U$2") (pin "P$10") (pinfunction "RSVD#0_P$10") (pintype "bidirectional"))
      (node (ref "U$2") (pin "P$12") (pinfunction "GND#1_P$12") (pintype "bidirectional"))
      (node (ref "U$2") (pin "P$13") (pinfunction "GND#2_P$13") (pintype "bidirectional"))
      (node (ref "U$2") (pin "P$16") (pinfunction "GND#3_P$16") (pintype "bidirectional"))
      (node (ref "U$2") (pin "P$5") (pinfunction "GND#0_P$5") (pintype "bidirectional"))
      (node (ref "U$21") (pin "P$8") (pinfunction "GND_P$8") (pintype "bidirectional"))
      (node (ref "U$22") (pin "P$2") (pinfunction "AD0/VOUT_P$2") (pintype "bidirectional"))
      (node (ref "U$22") (pin "P$3") (pinfunction "GNDD_P$3") (pintype "bidirectional"))
      (node (ref "U$22") (pin "P$4") (pinfunction "GNDA_P$4") (pintype "bidirectional"))
      (node (ref "U$22") (pin "P$7") (pinfunction "VINN_P$7") (pintype "bidirectional"))
      (node (ref "U$3") (pin "P$10") (pinfunction "RSVD$1_P$10") (pintype "bidirectional"))
      (node (ref "U$3") (pin "P$11") (pinfunction "RSVD$2_P$11") (pintype "bidirectional"))
      (node (ref "U$3") (pin "P$12") (pinfunction "GND$0_P$12") (pintype "bidirectional"))
      (node (ref "U$3") (pin "P$13") (pinfunction "GND$1_P$13") (pintype "bidirectional"))
      (node (ref "U$3") (pin "P$9") (pinfunction "RSVD$0_P$9") (pintype "bidirectional"))
      (node (ref "U$4") (pin "P$10") (pinfunction "RSVD_P$10") (pintype "bidirectional"))
      (node (ref "U$4") (pin "P$11") (pinfunction "INT1_P$11") (pintype "bidirectional"))
      (node (ref "U$4") (pin "P$12") (pinfunction "GND$1_P$12") (pintype "bidirectional"))
      (node (ref "U$4") (pin "P$13") (pinfunction "GND$2_P$13") (pintype "bidirectional"))
      (node (ref "U$4") (pin "P$16") (pinfunction "GND$3_P$16") (pintype "bidirectional"))
      (node (ref "U$4") (pin "P$5") (pinfunction "GND$0_P$5") (pintype "bidirectional"))
      (node (ref "U$5") (pin "P$3") (pinfunction "GND_P$3") (pintype "bidirectional"))
      (node (ref "U$6") (pin "P$10") (pinfunction "RSVD_P$10") (pintype "bidirectional"))
      (node (ref "U$6") (pin "P$12") (pinfunction "GND$1_P$12") (pintype "bidirectional"))
      (node (ref "U$6") (pin "P$13") (pinfunction "GND$2_P$13") (pintype "bidirectional"))
      (node (ref "U$6") (pin "P$16") (pinfunction "GND$3_P$16") (pintype "bidirectional"))
      (node (ref "U$6") (pin "P$5") (pinfunction "GND$0_P$5") (pintype "bidirectional"))
      (node (ref "U$8") (pin "P$1") (pinfunction "NC_P$1") (pintype "bidirectional"))
      (node (ref "U$8") (pin "P$2") (pinfunction "GND$0_P$2") (pintype "bidirectional"))
      (node (ref "U$8") (pin "P$5") (pinfunction "GND$1_P$5") (pintype "bidirectional"))
      (node (ref "U$9") (pin "P$10") (pinfunction "RES_P$10") (pintype "bidirectional"))
      (node (ref "U$9") (pin "P$12") (pinfunction "GND$1_P$12") (pintype "bidirectional"))
      (node (ref "U$9") (pin "P$5") (pinfunction "GND$0_P$5") (pintype "bidirectional"))
    )
    (net (code "6") (name "IND-LED-1") (class "Default")
      (node (ref "LED2") (pin "A") (pinfunction "A_A") (pintype "passive"))
      (node (ref "U$11") (pin "P$59") (pinfunction "PE4_P$59") (pintype "bidirectional"))
    )
    (net (code "7") (name "IND-LED-2") (class "Default")
      (node (ref "LED3") (pin "A") (pinfunction "A_A") (pintype "passive"))
      (node (ref "U$11") (pin "P$58") (pinfunction "PB4_P$58") (pintype "bidirectional"))
    )
    (net (code "8") (name "IND-LED-3") (class "Default")
      (node (ref "LED4") (pin "A") (pinfunction "A_A") (pintype "passive"))
      (node (ref "U$11") (pin "P$57") (pinfunction "PB5_P$57") (pintype "bidirectional"))
    )
    (net (code "9") (name "INT1-L3GD") (class "Default")
      (node (ref "U$11") (pin "P$15") (pinfunction "PC5_P$15") (pintype "bidirectional"))
      (node (ref "U$3") (pin "P$7") (pinfunction "INT1_P$7") (pintype "bidirectional"))
    )
    (net (code "10") (name "INT1-MAG3110") (class "Default")
      (node (ref "U$1") (pin "P$9") (pinfunction "INT1_P$9") (pintype "bidirectional"))
      (node (ref "U$11") (pin "P$1") (pinfunction "PB6_P$1") (pintype "bidirectional"))
    )
    (net (code "11") (name "INT1-MPL311") (class "Default")
      (node (ref "U$11") (pin "P$5") (pinfunction "PF4_P$5") (pintype "bidirectional"))
      (node (ref "U$5") (pin "P$6") (pinfunction "INT1_P$6") (pintype "bidirectional"))
    )
    (net (code "12") (name "INT2-ADXL362") (class "Default")
      (node (ref "U$10") (pin "P$9") (pinfunction "INT2_P$9") (pintype "bidirectional"))
      (node (ref "U$11") (pin "P$4") (pinfunction "PB7_P$4") (pintype "bidirectional"))
    )
    (net (code "13") (name "INT2-H3LIS331") (class "Default")
      (node (ref "U$11") (pin "P$9") (pinfunction "PE0_P$9") (pintype "bidirectional"))
      (node (ref "U$2") (pin "P$9") (pinfunction "INT2_P$9") (pintype "bidirectional"))
    )
    (net (code "14") (name "INT2-LIS3DH") (class "Default")
      (node (ref "U$11") (pin "P$14") (pinfunction "PC6_P$14") (pintype "bidirectional"))
      (node (ref "U$9") (pin "P$9") (pinfunction "INT2_P$9") (pintype "bidirectional"))
    )
    (net (code "15") (name "INT2-LPS331") (class "Default")
      (node (ref "U$11") (pin "P$16") (pinfunction "PC4_P$16") (pintype "bidirectional"))
      (node (ref "U$4") (pin "P$9") (pinfunction "INT2_P$9") (pintype "bidirectional"))
    )
    (net (code "16") (name "INT2-LSM303") (class "Default")
      (node (ref "U$11") (pin "P$10") (pinfunction "PD7_P$10") (pintype "bidirectional"))
      (node (ref "U$6") (pin "P$9") (pinfunction "INT2_P$9") (pintype "bidirectional"))
    )
    (net (code "17") (name "INT2-MAX21000") (class "Default")
      (node (ref "U$11") (pin "P$13") (pinfunction "PC7_P$13") (pintype "bidirectional"))
      (node (ref "U$19") (pin "P$9") (pinfunction "INT2_P$9") (pintype "bidirectional"))
    )
    (net (code "18") (name "LSM9D-DEN-G") (class "Default")
      (node (ref "U$17") (pin "P$10") (pinfunction "DEN_G_P$10") (pintype "bidirectional"))
    )
    (net (code "19") (name "LSM9D-DRGY-G") (class "Default")
      (node (ref "U$11") (pin "P$8") (pinfunction "PE1_P$8") (pintype "bidirectional"))
      (node (ref "U$17") (pin "P$12") (pinfunction "DRDY_G_P$12") (pintype "bidirectional"))
    )
    (net (code "20") (name "LSM9D-INT1-XM") (class "Default")
      (node (ref "U$11") (pin "P$7") (pinfunction "PE2_P$7") (pintype "bidirectional"))
      (node (ref "U$17") (pin "P$13") (pinfunction "INT1_XM_P$13") (pintype "bidirectional"))
    )
    (net (code "21") (name "LSM9D-INT2-XM") (class "Default")
      (node (ref "U$11") (pin "P$6") (pinfunction "PE3_P$6") (pintype "bidirectional"))
      (node (ref "U$17") (pin "P$14") (pinfunction "INT2_XM_P$14") (pintype "bidirectional"))
    )
    (net (code "22") (name "MISO-A") (class "Default")
      (node (ref "U$11") (pin "P$28") (pinfunction "PF0_P$28") (pintype "bidirectional"))
      (node (ref "U$14") (pin "P$8") (pinfunction "A7_P$8") (pintype "bidirectional"))
    )
    (net (code "23") (name "MISO-B") (class "Default")
      (node (ref "R6") (pin "1") (pinfunction "1_1") (pintype "passive"))
      (node (ref "U$10") (pin "P$7") (pinfunction "MISO_P$7") (pintype "bidirectional"))
      (node (ref "U$14") (pin "P$13") (pinfunction "B7_P$13") (pintype "bidirectional"))
      (node (ref "U$15") (pin "P$6") (pinfunction "DOUT_P$6") (pintype "bidirectional"))
      (node (ref "U$17") (pin "P$22") (pinfunction "SDO_G_P$22") (pintype "bidirectional"))
      (node (ref "U$17") (pin "P$23") (pinfunction "SDO_XM_P$23") (pintype "bidirectional"))
      (node (ref "U$19") (pin "P$7") (pinfunction "MISO_P$7") (pintype "bidirectional"))
      (node (ref "U$2") (pin "P$7") (pinfunction "MISO_P$7") (pintype "bidirectional"))
      (node (ref "U$3") (pin "P$4") (pinfunction "MISO_P$4") (pintype "bidirectional"))
      (node (ref "U$4") (pin "P$7") (pinfunction "MISO_P$7") (pintype "bidirectional"))
      (node (ref "U$6") (pin "P$7") (pinfunction "MISO_P$7") (pintype "bidirectional"))
      (node (ref "U$9") (pin "P$7") (pinfunction "MISO_P$7") (pintype "bidirectional"))
    )
    (net (code "24") (name "MOSI-A") (class "Default")
      (node (ref "U$11") (pin "P$29") (pinfunction "PF1_P$29") (pintype "bidirectional"))
      (node (ref "U$14") (pin "P$7") (pinfunction "A6_P$7") (pintype "bidirectional"))
    )
    (net (code "25") (name "MOSI-B") (class "Default")
      (node (ref "R4") (pin "1") (pinfunction "1_1") (pintype "passive"))
      (node (ref "U$10") (pin "P$6") (pinfunction "MOSI_P$6") (pintype "bidirectional"))
      (node (ref "U$14") (pin "P$14") (pinfunction "B6_P$14") (pintype "bidirectional"))
      (node (ref "U$15") (pin "P$2") (pinfunction "DIN_P$2") (pintype "bidirectional"))
      (node (ref "U$17") (pin "P$24") (pinfunction "SDA_P$24") (pintype "bidirectional"))
      (node (ref "U$19") (pin "P$6") (pinfunction "MOSI_P$6") (pintype "bidirectional"))
      (node (ref "U$2") (pin "P$6") (pinfunction "MOSI_P$6") (pintype "bidirectional"))
      (node (ref "U$3") (pin "P$3") (pinfunction "MOSI_P$3") (pintype "bidirectional"))
      (node (ref "U$4") (pin "P$6") (pinfunction "MOSI_P$6") (pintype "bidirectional"))
      (node (ref "U$6") (pin "P$6") (pinfunction "MOSI_P$6") (pintype "bidirectional"))
      (node (ref "U$9") (pin "P$6") (pinfunction "MOSI_P$6") (pintype "bidirectional"))
    )
    (net (code "26") (name "Net-(C24-Pad2)") (class "Default")
      (node (ref "C24") (pin "2") (pinfunction "2_2") (pintype "passive"))
      (node (ref "R10") (pin "1") (pinfunction "1_1") (pintype "passive"))
    )
    (net (code "27") (name "Net-(IC1A-IN)") (class "Default")
      (node (ref "IC1") (pin "1") (pinfunction "IN_1") (pintype "input"))
      (node (ref "IC2") (pin "1") (pinfunction "IN_1") (pintype "input"))
      (node (ref "IC4") (pin "1") (pinfunction "IN_1") (pintype "input"))
      (node (ref "S1") (pin "1") (pinfunction "O_1") (pintype "passive"))
    )
    (net (code "28") (name "Net-(J1-2)") (class "Default")
      (node (ref "J1") (pin "P$2") (pinfunction "2_P$2") (pintype "bidirectional"))
      (node (ref "S1") (pin "2") (pinfunction "P_2") (pintype "passive"))
    )
    (net (code "29") (name "Net-(LED1-PadA)") (class "Default")
      (node (ref "LED1") (pin "A") (pinfunction "A_A") (pintype "passive"))
      (node (ref "R7") (pin "1") (pinfunction "1_1") (pintype "passive"))
    )
    (net (code "30") (name "Net-(LED2-PadC)") (class "Default")
      (node (ref "LED2") (pin "C") (pinfunction "C_C") (pintype "passive"))
      (node (ref "R12") (pin "2") (pinfunction "2_2") (pintype "passive"))
    )
    (net (code "31") (name "Net-(LED3-PadC)") (class "Default")
      (node (ref "LED3") (pin "C") (pinfunction "C_C") (pintype "passive"))
      (node (ref "R13") (pin "2") (pinfunction "2_2") (pintype "passive"))
    )
    (net (code "32") (name "Net-(LED4-PadC)") (class "Default")
      (node (ref "LED4") (pin "C") (pinfunction "C_C") (pintype "passive"))
      (node (ref "R14") (pin "2") (pinfunction "2_2") (pintype "passive"))
    )
    (net (code "33") (name "Net-(R3-Pad2)") (class "Default")
      (node (ref "R3") (pin "2") (pinfunction "2_2") (pintype "passive"))
      (node (ref "TP1") (pin "P$1") (pinfunction "P$1_P$1") (pintype "bidirectional"))
    )
    (net (code "34") (name "Net-(R4-Pad2)") (class "Default")
      (node (ref "R4") (pin "2") (pinfunction "2_2") (pintype "passive"))
      (node (ref "TP2") (pin "P$1") (pinfunction "P$1_P$1") (pintype "bidirectional"))
    )
    (net (code "35") (name "Net-(R5-Pad2)") (class "Default")
      (node (ref "R5") (pin "2") (pinfunction "2_2") (pintype "passive"))
      (node (ref "TP6") (pin "P$1") (pinfunction "P$1_P$1") (pintype "bidirectional"))
    )
    (net (code "36") (name "Net-(R6-Pad2)") (class "Default")
      (node (ref "R6") (pin "2") (pinfunction "2_2") (pintype "passive"))
      (node (ref "TP3") (pin "P$1") (pinfunction "P$1_P$1") (pintype "bidirectional"))
    )
    (net (code "37") (name "Net-(R8-Pad2)") (class "Default")
      (node (ref "R8") (pin "2") (pinfunction "2_2") (pintype "passive"))
      (node (ref "TP5") (pin "P$1") (pinfunction "P$1_P$1") (pintype "bidirectional"))
    )
    (net (code "38") (name "Net-(U$1-CAP-A)") (class "Default")
      (node (ref "C1") (pin "1") (pinfunction "1_1") (pintype "passive"))
      (node (ref "U$1") (pin "P$1") (pinfunction "CAP-A_P$1") (pintype "bidirectional"))
    )
    (net (code "39") (name "Net-(U$1-CAP-R)") (class "Default")
      (node (ref "C4") (pin "1") (pinfunction "1_1") (pintype "passive"))
      (node (ref "U$1") (pin "P$4") (pinfunction "CAP-R_P$4") (pintype "bidirectional"))
    )
    (net (code "40") (name "Net-(U$3-CAP)") (class "Default")
      (node (ref "C10") (pin "1") (pinfunction "1_1") (pintype "passive"))
      (node (ref "U$3") (pin "P$14") (pinfunction "CAP_P$14") (pintype "bidirectional"))
    )
    (net (code "41") (name "Net-(U$5-CAP)") (class "Default")
      (node (ref "C17") (pin "1") (pinfunction "1_1") (pintype "passive"))
      (node (ref "U$5") (pin "P$2") (pinfunction "CAP_P$2") (pintype "bidirectional"))
    )
    (net (code "42") (name "Net-(U$6-C1)") (class "Default")
      (node (ref "C18") (pin "1") (pinfunction "1_1") (pintype "passive"))
      (node (ref "U$6") (pin "P$15") (pinfunction "C1_P$15") (pintype "bidirectional"))
    )
    (net (code "43") (name "Net-(U$6-SETC)") (class "Default")
      (node (ref "C21") (pin "2") (pinfunction "2_2") (pintype "passive"))
      (node (ref "U$6") (pin "P$2") (pinfunction "SETC_P$2") (pintype "bidirectional"))
    )
    (net (code "44") (name "Net-(U$6-SETP)") (class "Default")
      (node (ref "C21") (pin "1") (pinfunction "1_1") (pintype "passive"))
      (node (ref "U$6") (pin "P$3") (pinfunction "SETP_P$3") (pintype "bidirectional"))
    )
    (net (code "45") (name "Net-(U$11-OSC0)") (class "Default")
      (node (ref "C44") (pin "1") (pinfunction "1_1") (pintype "passive"))
      (node (ref "U$11") (pin "P$40") (pinfunction "OSC0_P$40") (pintype "bidirectional"))
      (node (ref "U$13") (pin "P$3") (pinfunction "B_P$3") (pintype "bidirectional"))
    )
    (net (code "46") (name "Net-(U$11-OSC1)") (class "Default")
      (node (ref "R16") (pin "1") (pinfunction "1_1") (pintype "passive"))
      (node (ref "U$11") (pin "P$41") (pinfunction "OSC1_P$41") (pintype "bidirectional"))
    )
    (net (code "47") (name "Net-(U$11-XOSC1)") (class "Default")
      (node (ref "C42") (pin "2") (pinfunction "2_2") (pintype "passive"))
      (node (ref "U$11") (pin "P$36") (pinfunction "XOSC1_P$36") (pintype "bidirectional"))
      (node (ref "U$12") (pin "P$2") (pinfunction "P$2_P$2") (pintype "bidirectional"))
    )
    (net (code "48") (name "Net-(U$11-XOSCO)") (class "Default")
      (node (ref "C41") (pin "1") (pinfunction "1_1") (pintype "passive"))
      (node (ref "U$11") (pin "P$34") (pinfunction "XOSCO_P$34") (pintype "bidirectional"))
      (node (ref "U$12") (pin "P$1") (pinfunction "P$1_P$1") (pintype "bidirectional"))
    )
    (net (code "49") (name "Net-(U$11-~{RST})") (class "Default")
      (node (ref "C30") (pin "2") (pinfunction "2_2") (pintype "passive"))
      (node (ref "R17") (pin "1") (pinfunction "1_1") (pintype "passive"))
      (node (ref "U$11") (pin "P$38") (pinfunction "~{RST}_P$38") (pintype "bidirectional"))
    )
    (net (code "50") (name "Net-(U$13-A)") (class "Default")
      (node (ref "C43") (pin "1") (pinfunction "1_1") (pintype "passive"))
      (node (ref "R16") (pin "2") (pinfunction "2_2") (pintype "passive"))
      (node (ref "U$13") (pin "P$1") (pinfunction "A_P$1") (pintype "bidirectional"))
    )
    (net (code "51") (name "Net-(U$17-C1_XM)") (class "Default")
      (node (ref "C48") (pin "1") (pinfunction "1_1") (pintype "passive"))
      (node (ref "U$17") (pin "P$7") (pinfunction "C1_XM_P$7") (pintype "bidirectional"))
    )
    (net (code "52") (name "Net-(U$17-SETC_XM)") (class "Default")
      (node (ref "C49") (pin "2") (pinfunction "2_2") (pintype "passive"))
      (node (ref "U$17") (pin "P$8") (pinfunction "SETC_XM_P$8") (pintype "bidirectional"))
    )
    (net (code "53") (name "Net-(U$17-SETP_XM)") (class "Default")
      (node (ref "C49") (pin "1") (pinfunction "1_1") (pintype "passive"))
      (node (ref "U$17") (pin "P$9") (pinfunction "SETP_XM_P$9") (pintype "bidirectional"))
    )
    (net (code "54") (name "Net-(U$22-VINP)") (class "Default")
      (node (ref "R11") (pin "2") (pinfunction "2_2") (pintype "passive"))
      (node (ref "R9") (pin "1") (pinfunction "1_1") (pintype "passive"))
      (node (ref "U$22") (pin "P$6") (pinfunction "VINP_P$6") (pintype "bidirectional"))
    )
    (net (code "55") (name "SCL-0") (class "Default")
      (node (ref "R1") (pin "1") (pinfunction "1_1") (pintype "passive"))
      (node (ref "R5") (pin "1") (pinfunction "1_1") (pintype "passive"))
      (node (ref "U$1") (pin "P$7") (pinfunction "SCL_P$7") (pintype "bidirectional"))
      (node (ref "U$11") (pin "P$23") (pinfunction "PA6_P$23") (pintype "bidirectional"))
      (node (ref "U$22") (pin "P$10") (pinfunction "SCL_P$10") (pintype "bidirectional"))
      (node (ref "U$5") (pin "P$8") (pinfunction "SCL_P$8") (pintype "bidirectional"))
    )
    (net (code "56") (name "SCLK-A") (class "Default")
      (node (ref "U$11") (pin "P$30") (pinfunction "PF2_P$30") (pintype "bidirectional"))
      (node (ref "U$14") (pin "P$6") (pinfunction "A5_P$6") (pintype "bidirectional"))
    )
    (net (code "57") (name "SCLK-B") (class "Default")
      (node (ref "R3") (pin "1") (pinfunction "1_1") (pintype "passive"))
      (node (ref "U$10") (pin "P$4") (pinfunction "SCLK_P$4") (pintype "bidirectional"))
      (node (ref "U$14") (pin "P$15") (pinfunction "B5_P$15") (pintype "bidirectional"))
      (node (ref "U$15") (pin "P$4") (pinfunction "SCLK_P$4") (pintype "bidirectional"))
      (node (ref "U$17") (pin "P$21") (pinfunction "SCL_P$21") (pintype "bidirectional"))
      (node (ref "U$19") (pin "P$4") (pinfunction "SCLK_P$4") (pintype "bidirectional"))
      (node (ref "U$2") (pin "P$4") (pinfunction "SCLK_P$4") (pintype "bidirectional"))
      (node (ref "U$3") (pin "P$2") (pinfunction "SCL_P$2") (pintype "bidirectional"))
      (node (ref "U$4") (pin "P$4") (pinfunction "SCL_P$4") (pintype "bidirectional"))
      (node (ref "U$6") (pin "P$4") (pinfunction "SCL_P$4") (pintype "bidirectional"))
      (node (ref "U$9") (pin "P$4") (pinfunction "SCL_P$4") (pintype "bidirectional"))
    )
    (net (code "58") (name "SD-CARD-INSERT") (class "Default")
      (node (ref "U$11") (pin "P$60") (pinfunction "PE5_P$60") (pintype "bidirectional"))
      (node (ref "U$18") (pin "P$8") (pinfunction "SWITCH2_P$8") (pintype "bidirectional"))
    )
    (net (code "59") (name "SD-CS") (class "Default")
      (node (ref "U$11") (pin "P$62") (pinfunction "PD1_P$62") (pintype "bidirectional"))
      (node (ref "U$18") (pin "P$2") (pinfunction "~{CS}_P$2") (pintype "bidirectional"))
    )
    (net (code "60") (name "SD-MISO") (class "Default")
      (node (ref "U$11") (pin "P$63") (pinfunction "PD2_P$63") (pintype "bidirectional"))
      (node (ref "U$18") (pin "P$7") (pinfunction "D0_P$7") (pintype "bidirectional"))
    )
    (net (code "61") (name "SD-MOSI") (class "Default")
      (node (ref "U$11") (pin "P$64") (pinfunction "PD3_P$64") (pintype "bidirectional"))
      (node (ref "U$18") (pin "P$3") (pinfunction "DI_P$3") (pintype "bidirectional"))
    )
    (net (code "62") (name "SD-SCLK") (class "Default")
      (node (ref "U$11") (pin "P$61") (pinfunction "PD0_P$61") (pintype "bidirectional"))
      (node (ref "U$18") (pin "P$5") (pinfunction "SCLK_P$5") (pintype "bidirectional"))
    )
    (net (code "63") (name "SDA-0") (class "Default")
      (node (ref "R2") (pin "1") (pinfunction "1_1") (pintype "passive"))
      (node (ref "R8") (pin "1") (pinfunction "1_1") (pintype "passive"))
      (node (ref "U$1") (pin "P$6") (pinfunction "SDA_P$6") (pintype "bidirectional"))
      (node (ref "U$11") (pin "P$24") (pinfunction "PA7_P$24") (pintype "bidirectional"))
      (node (ref "U$22") (pin "P$1") (pinfunction "SDA_P$1") (pintype "bidirectional"))
      (node (ref "U$5") (pin "P$7") (pinfunction "SDA_P$7") (pintype "bidirectional"))
    )
    (net (code "64") (name "SPI-ADDR0") (class "Default")
      (node (ref "U$11") (pin "P$17") (pinfunction "PA0_P$17") (pintype "bidirectional"))
      (node (ref "U$21") (pin "P$15") (pinfunction "A_P$15") (pintype "bidirectional"))
    )
    (net (code "65") (name "SPI-ADDR1") (class "Default")
      (node (ref "U$11") (pin "P$18") (pinfunction "PA1_P$18") (pintype "bidirectional"))
      (node (ref "U$21") (pin "P$14") (pinfunction "B_P$14") (pintype "bidirectional"))
    )
    (net (code "66") (name "SPI-ADDR2") (class "Default")
      (node (ref "U$11") (pin "P$19") (pinfunction "PA2_P$19") (pintype "bidirectional"))
      (node (ref "U$21") (pin "P$13") (pinfunction "C_P$13") (pintype "bidirectional"))
    )
    (net (code "67") (name "SPI-ADDR3") (class "Default")
      (node (ref "U$11") (pin "P$20") (pinfunction "PA3_P$20") (pintype "bidirectional"))
      (node (ref "U$21") (pin "P$12") (pinfunction "D_P$12") (pintype "bidirectional"))
    )
    (net (code "68") (name "SPI-ENABLE") (class "Default")
      (node (ref "U$11") (pin "P$31") (pinfunction "PF3_P$31") (pintype "bidirectional"))
      (node (ref "U$14") (pin "P$10") (pinfunction "OE_P$10") (pintype "bidirectional"))
    )
    (net (code "69") (name "SWCLK") (class "Default")
      (node (ref "U$11") (pin "P$52") (pinfunction "PC0_P$52") (pintype "bidirectional"))
      (node (ref "U$7") (pin "P$1") (pinfunction "1_P$1") (pintype "bidirectional"))
    )
    (net (code "70") (name "SWDIO") (class "Default")
      (node (ref "U$11") (pin "P$51") (pinfunction "PC1_P$51") (pintype "bidirectional"))
      (node (ref "U$7") (pin "P$2") (pinfunction "2_P$2") (pintype "bidirectional"))
    )
    (net (code "71") (name "SWO") (class "Default")
      (node (ref "U$11") (pin "P$49") (pinfunction "PC3_P$49") (pintype "bidirectional"))
      (node (ref "U$7") (pin "P$4") (pinfunction "4_P$4") (pintype "bidirectional"))
    )
    (net (code "72") (name "TDI") (class "Default")
      (node (ref "U$11") (pin "P$50") (pinfunction "PC2_P$50") (pintype "bidirectional"))
      (node (ref "U$7") (pin "P$3") (pinfunction "3_P$3") (pintype "bidirectional"))
    )
    (net (code "73") (name "U1RX") (class "Default")
      (node (ref "TP8") (pin "P$1") (pinfunction "P$1_P$1") (pintype "bidirectional"))
      (node (ref "U$11") (pin "P$45") (pinfunction "PB0_P$45") (pintype "bidirectional"))
    )
    (net (code "74") (name "U1TX") (class "Default")
      (node (ref "TP7") (pin "P$1") (pinfunction "P$1_P$1") (pintype "bidirectional"))
      (node (ref "U$11") (pin "P$46") (pinfunction "PB1_P$46") (pintype "bidirectional"))
    )
    (net (code "75") (name "unconnected-(IC1A-OUT-Pad3)") (class "Default")
      (node (ref "IC1") (pin "3") (pinfunction "OUT_3") (pintype "output"))
    )
    (net (code "76") (name "unconnected-(S1-S-Pad3)") (class "Default")
      (node (ref "S1") (pin "3") (pinfunction "S_3") (pintype "passive"))
    )
    (net (code "77") (name "unconnected-(U$1-NC-PadP$3)") (class "Default")
      (node (ref "U$1") (pin "P$3") (pinfunction "NC_P$3") (pintype "bidirectional"))
    )
    (net (code "78") (name "unconnected-(U$2-INT1-PadP$11)") (class "Default")
      (node (ref "U$2") (pin "P$11") (pinfunction "INT1_P$11") (pintype "bidirectional"))
    )
    (net (code "79") (name "unconnected-(U$2-NC#0-PadP$2)") (class "Default")
      (node (ref "U$2") (pin "P$2") (pinfunction "NC#0_P$2") (pintype "bidirectional"))
    )
    (net (code "80") (name "unconnected-(U$2-NC#1-PadP$3)") (class "Default")
      (node (ref "U$2") (pin "P$3") (pinfunction "NC#1_P$3") (pintype "bidirectional"))
    )
    (net (code "81") (name "unconnected-(U$3-INT2-PadP$6)") (class "Default")
      (node (ref "U$3") (pin "P$6") (pinfunction "INT2_P$6") (pintype "bidirectional"))
    )
    (net (code "82") (name "unconnected-(U$4-NC$0-PadP$2)") (class "Default")
      (node (ref "U$4") (pin "P$2") (pinfunction "NC$0_P$2") (pintype "bidirectional"))
    )
    (net (code "83") (name "unconnected-(U$4-NC$1-PadP$3)") (class "Default")
      (node (ref "U$4") (pin "P$3") (pinfunction "NC$1_P$3") (pintype "bidirectional"))
    )
    (net (code "84") (name "unconnected-(U$5-INT2-PadP$5)") (class "Default")
      (node (ref "U$5") (pin "P$5") (pinfunction "INT2_P$5") (pintype "bidirectional"))
    )
    (net (code "85") (name "unconnected-(U$6-INT1-PadP$11)") (class "Default")
      (node (ref "U$6") (pin "P$11") (pinfunction "INT1_P$11") (pintype "bidirectional"))
    )
    (net (code "86") (name "unconnected-(U$9-ADC1-PadP$16)") (class "Default")
      (node (ref "U$9") (pin "P$16") (pinfunction "ADC1_P$16") (pintype "bidirectional"))
    )
    (net (code "87") (name "unconnected-(U$9-ADC2-PadP$15)") (class "Default")
      (node (ref "U$9") (pin "P$15") (pinfunction "ADC2_P$15") (pintype "bidirectional"))
    )
    (net (code "88") (name "unconnected-(U$9-ADC3-PadP$13)") (class "Default")
      (node (ref "U$9") (pin "P$13") (pinfunction "ADC3_P$13") (pintype "bidirectional"))
    )
    (net (code "89") (name "unconnected-(U$9-INT1-PadP$11)") (class "Default")
      (node (ref "U$9") (pin "P$11") (pinfunction "INT1_P$11") (pintype "bidirectional"))
    )
    (net (code "90") (name "unconnected-(U$9-NC$0-PadP$2)") (class "Default")
      (node (ref "U$9") (pin "P$2") (pinfunction "NC$0_P$2") (pintype "bidirectional"))
    )
    (net (code "91") (name "unconnected-(U$9-NC$1-PadP$3)") (class "Default")
      (node (ref "U$9") (pin "P$3") (pinfunction "NC$1_P$3") (pintype "bidirectional"))
    )
    (net (code "92") (name "unconnected-(U$10-INT1-PadP$11)") (class "Default")
      (node (ref "U$10") (pin "P$11") (pinfunction "INT1_P$11") (pintype "bidirectional"))
    )
    (net (code "93") (name "unconnected-(U$10-NC$0-PadP$2)") (class "Default")
      (node (ref "U$10") (pin "P$2") (pinfunction "NC$0_P$2") (pintype "bidirectional"))
    )
    (net (code "94") (name "unconnected-(U$10-NC$1-PadP$15)") (class "Default")
      (node (ref "U$10") (pin "P$15") (pinfunction "NC$1_P$15") (pintype "bidirectional"))
    )
    (net (code "95") (name "unconnected-(U$10-RSVD$0-PadP$3)") (class "Default")
      (node (ref "U$10") (pin "P$3") (pinfunction "RSVD$0_P$3") (pintype "bidirectional"))
    )
    (net (code "96") (name "unconnected-(U$10-RSVD$2-PadP$10)") (class "Default")
      (node (ref "U$10") (pin "P$10") (pinfunction "RSVD$2_P$10") (pintype "bidirectional"))
    )
    (net (code "97") (name "unconnected-(U$11-PA4-PadP$21)") (class "Default")
      (node (ref "U$11") (pin "P$21") (pinfunction "PA4_P$21") (pintype "bidirectional"))
    )
    (net (code "98") (name "unconnected-(U$11-PA5-PadP$22)") (class "Default")
      (node (ref "U$11") (pin "P$22") (pinfunction "PA5_P$22") (pintype "bidirectional"))
    )
    (net (code "99") (name "unconnected-(U$11-PB2-PadP$47)") (class "Default")
      (node (ref "U$11") (pin "P$47") (pinfunction "PB2_P$47") (pintype "bidirectional"))
    )
    (net (code "100") (name "unconnected-(U$11-PD4-PadP$43)") (class "Default")
      (node (ref "U$11") (pin "P$43") (pinfunction "PD4_P$43") (pintype "bidirectional"))
    )
    (net (code "101") (name "unconnected-(U$11-PD5-PadP$44)") (class "Default")
      (node (ref "U$11") (pin "P$44") (pinfunction "PD5_P$44") (pintype "bidirectional"))
    )
    (net (code "102") (name "unconnected-(U$11-PD6-PadP$53)") (class "Default")
      (node (ref "U$11") (pin "P$53") (pinfunction "PD6_P$53") (pintype "bidirectional"))
    )
    (net (code "103") (name "unconnected-(U$11-~{HIB}-PadP$33)") (class "Default")
      (node (ref "U$11") (pin "P$33") (pinfunction "~{HIB}_P$33") (pintype "bidirectional"))
    )
    (net (code "104") (name "unconnected-(U$11-~{WAKE}-PadP$32)") (class "Default")
      (node (ref "U$11") (pin "P$32") (pinfunction "~{WAKE}_P$32") (pintype "bidirectional"))
    )
    (net (code "105") (name "unconnected-(U$14-A1-PadP$1)") (class "Default")
      (node (ref "U$14") (pin "P$1") (pinfunction "A1_P$1") (pintype "bidirectional"))
    )
    (net (code "106") (name "unconnected-(U$14-A2-PadP$3)") (class "Default")
      (node (ref "U$14") (pin "P$3") (pinfunction "A2_P$3") (pintype "bidirectional"))
    )
    (net (code "107") (name "unconnected-(U$14-A3-PadP$4)") (class "Default")
      (node (ref "U$14") (pin "P$4") (pinfunction "A3_P$4") (pintype "bidirectional"))
    )
    (net (code "108") (name "unconnected-(U$14-A4-PadP$5)") (class "Default")
      (node (ref "U$14") (pin "P$5") (pinfunction "A4_P$5") (pintype "bidirectional"))
    )
    (net (code "109") (name "unconnected-(U$14-A8-PadP$9)") (class "Default")
      (node (ref "U$14") (pin "P$9") (pinfunction "A8_P$9") (pintype "bidirectional"))
    )
    (net (code "110") (name "unconnected-(U$14-B1-PadP$20)") (class "Default")
      (node (ref "U$14") (pin "P$20") (pinfunction "B1_P$20") (pintype "bidirectional"))
    )
    (net (code "111") (name "unconnected-(U$14-B2-PadP$18)") (class "Default")
      (node (ref "U$14") (pin "P$18") (pinfunction "B2_P$18") (pintype "bidirectional"))
    )
    (net (code "112") (name "unconnected-(U$14-B3-PadP$17)") (class "Default")
      (node (ref "U$14") (pin "P$17") (pinfunction "B3_P$17") (pintype "bidirectional"))
    )
    (net (code "113") (name "unconnected-(U$14-B4-PadP$16)") (class "Default")
      (node (ref "U$14") (pin "P$16") (pinfunction "B4_P$16") (pintype "bidirectional"))
    )
    (net (code "114") (name "unconnected-(U$14-B8-PadP$12)") (class "Default")
      (node (ref "U$14") (pin "P$12") (pinfunction "B8_P$12") (pintype "bidirectional"))
    )
    (net (code "115") (name "unconnected-(U$17-INT_G-PadP$11)") (class "Default")
      (node (ref "U$17") (pin "P$11") (pinfunction "INT_G_P$11") (pintype "bidirectional"))
    )
    (net (code "116") (name "unconnected-(U$17-RES#0-PadP$1)") (class "Default")
      (node (ref "U$17") (pin "P$1") (pinfunction "RES#0_P$1") (pintype "bidirectional"))
    )
    (net (code "117") (name "unconnected-(U$18-GND#1-PadP$10)") (class "Default")
      (node (ref "U$18") (pin "P$10") (pinfunction "GND#1_P$10") (pintype "bidirectional"))
    )
    (net (code "118") (name "unconnected-(U$18-GND#2-PadP$11)") (class "Default")
      (node (ref "U$18") (pin "P$11") (pinfunction "GND#2_P$11") (pintype "bidirectional"))
    )
    (net (code "119") (name "unconnected-(U$18-GND#3-PadP$12)") (class "Default")
      (node (ref "U$18") (pin "P$12") (pinfunction "GND#3_P$12") (pintype "bidirectional"))
    )
    (net (code "120") (name "unconnected-(U$18-GND#4-PadP$13)") (class "Default")
      (node (ref "U$18") (pin "P$13") (pinfunction "GND#4_P$13") (pintype "bidirectional"))
    )
    (net (code "121") (name "unconnected-(U$18-RSV-PadP$1)") (class "Default")
      (node (ref "U$18") (pin "P$1") (pinfunction "RSV_P$1") (pintype "bidirectional"))
    )
    (net (code "122") (name "unconnected-(U$19-DSYNC-PadP$12)") (class "Default")
      (node (ref "U$19") (pin "P$12") (pinfunction "DSYNC_P$12") (pintype "bidirectional"))
    )
    (net (code "123") (name "unconnected-(U$19-INT1-PadP$11)") (class "Default")
      (node (ref "U$19") (pin "P$11") (pinfunction "INT1_P$11") (pintype "bidirectional"))
    )
    (net (code "124") (name "unconnected-(U$19-NC#0-PadP$2)") (class "Default")
      (node (ref "U$19") (pin "P$2") (pinfunction "NC#0_P$2") (pintype "bidirectional"))
    )
    (net (code "125") (name "unconnected-(U$19-NC#1-PadP$3)") (class "Default")
      (node (ref "U$19") (pin "P$3") (pinfunction "NC#1_P$3") (pintype "bidirectional"))
    )
    (net (code "126") (name "unconnected-(U$19-NC#2-PadP$16)") (class "Default")
      (node (ref "U$19") (pin "P$16") (pinfunction "NC#2_P$16") (pintype "bidirectional"))
    )
    (net (code "127") (name "unconnected-(U$19-RSVD#1-PadP$13)") (class "Default")
      (node (ref "U$19") (pin "P$13") (pinfunction "RSVD#1_P$13") (pintype "bidirectional"))
    )
    (net (code "128") (name "unconnected-(U$22-FLOAT-PadP$11)") (class "Default")
      (node (ref "U$22") (pin "P$11") (pinfunction "FLOAT_P$11") (pintype "bidirectional"))
    )
    (net (code "129") (name "~{CS-ADT7301}") (class "Default")
      (node (ref "U$15") (pin "P$5") (pinfunction "~{CS}_P$5") (pintype "bidirectional"))
      (node (ref "U$21") (pin "P$11") (pinfunction "9_P$11") (pintype "bidirectional"))
    )
    (net (code "130") (name "~{CS-ADXL362}") (class "Default")
      (node (ref "U$10") (pin "P$8") (pinfunction "~{CS}_P$8") (pintype "bidirectional"))
      (node (ref "U$21") (pin "P$1") (pinfunction "0_P$1") (pintype "bidirectional"))
    )
    (net (code "131") (name "~{CS-H3LIS331DLTR}") (class "Default")
      (node (ref "U$2") (pin "P$8") (pinfunction "~{CS}_P$8") (pintype "bidirectional"))
      (node (ref "U$21") (pin "P$2") (pinfunction "1_P$2") (pintype "bidirectional"))
    )
    (net (code "132") (name "~{CS-LIS3DH}") (class "Default")
      (node (ref "U$21") (pin "P$7") (pinfunction "6_P$7") (pintype "bidirectional"))
      (node (ref "U$9") (pin "P$8") (pinfunction "~{CS}_P$8") (pintype "bidirectional"))
    )
    (net (code "133") (name "~{CS-LPS331}") (class "Default")
      (node (ref "U$21") (pin "P$10") (pinfunction "8_P$10") (pintype "bidirectional"))
      (node (ref "U$4") (pin "P$8") (pinfunction "~{CS}_P$8") (pintype "bidirectional"))
    )
    (net (code "134") (name "~{CS-LS3GD20}") (class "Default")
      (node (ref "U$21") (pin "P$9") (pinfunction "7_P$9") (pintype "bidirectional"))
      (node (ref "U$3") (pin "P$5") (pinfunction "~{CS}_P$5") (pintype "bidirectional"))
    )
    (net (code "135") (name "~{CS-LSM9D30-G}") (class "Default")
      (node (ref "U$17") (pin "P$19") (pinfunction "~{CS_G}_P$19") (pintype "bidirectional"))
      (node (ref "U$21") (pin "P$3") (pinfunction "2_P$3") (pintype "bidirectional"))
    )
    (net (code "136") (name "~{CS-LSM9DS0-XM}") (class "Default")
      (node (ref "U$17") (pin "P$20") (pinfunction "~{CS_XM}_P$20") (pintype "bidirectional"))
      (node (ref "U$21") (pin "P$4") (pinfunction "3_P$4") (pintype "bidirectional"))
    )
    (net (code "137") (name "~{CS-LSM303}") (class "Default")
      (node (ref "U$21") (pin "P$6") (pinfunction "5_P$6") (pintype "bidirectional"))
      (node (ref "U$6") (pin "P$8") (pinfunction "~{CS}_P$8") (pintype "bidirectional"))
    )
    (net (code "138") (name "~{CS-MAX21000}") (class "Default")
      (node (ref "U$19") (pin "P$8") (pinfunction "~{CS}_P$8") (pintype "bidirectional"))
      (node (ref "U$21") (pin "P$5") (pinfunction "4_P$5") (pintype "bidirectional"))
    )
  )
)
